# SOC_SDRAM.net
KiCad netlist of a schematic drawn in Altium Designer
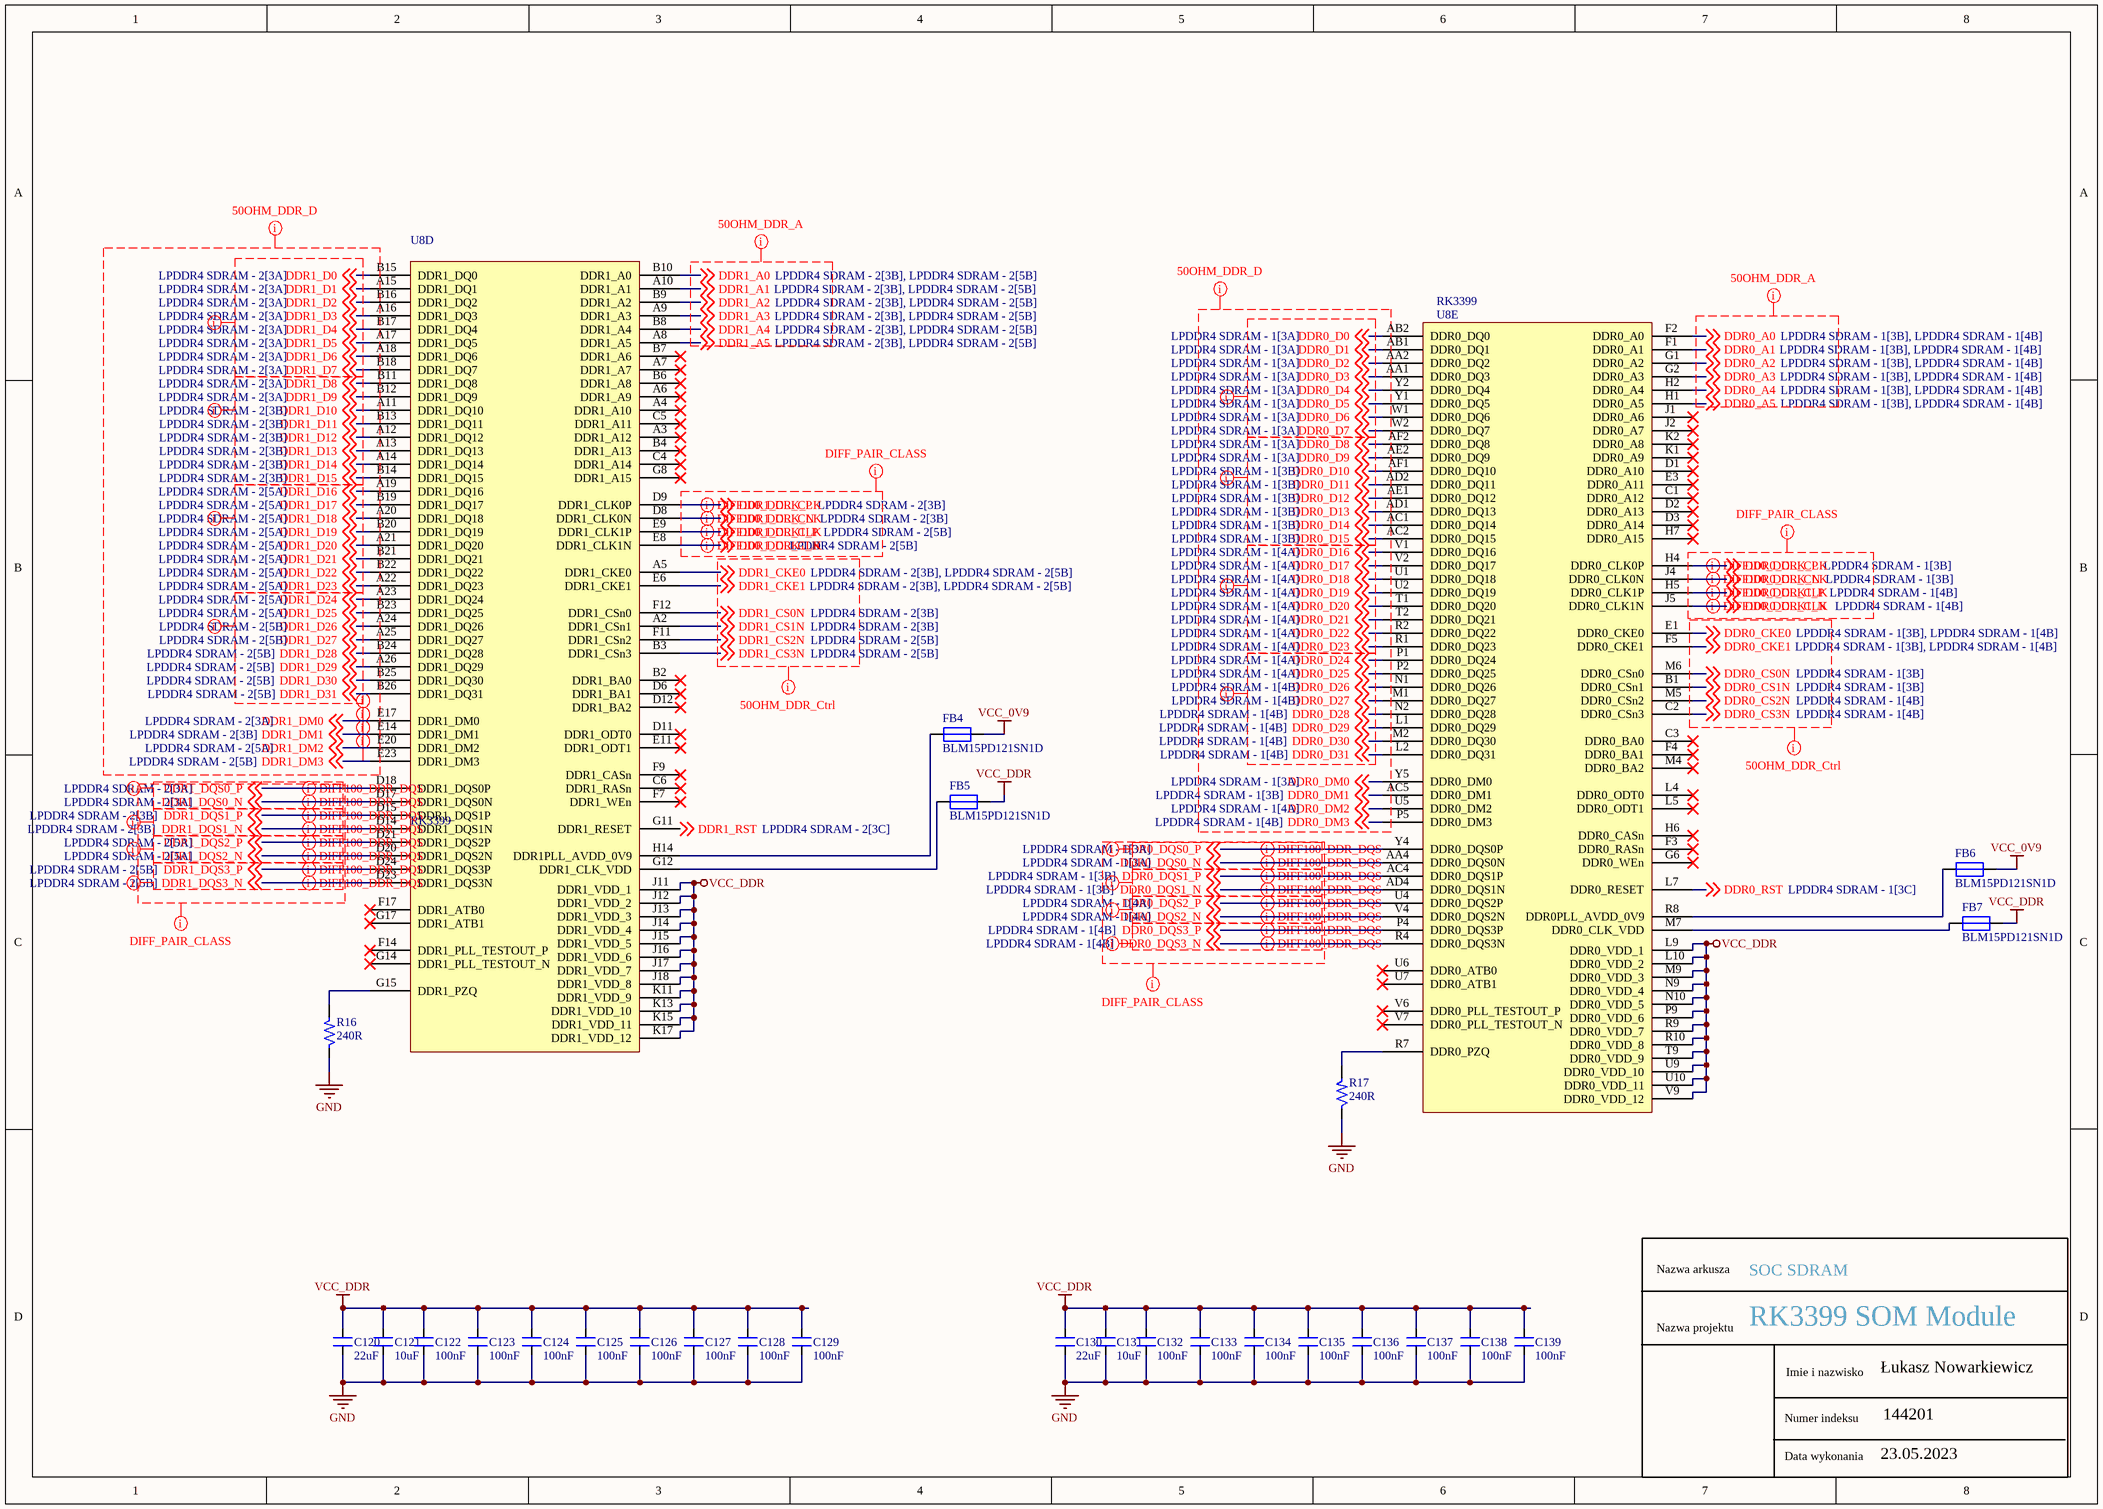
[diagram p0: SOC SDRAM.SchDoc]

(export (version "E")
  (design (tool "Eeschema 10.0.6"))
  (components
    (comp (ref "C120")
      (value "22uF")
      (footprint "CAP_0603")
      (description "22µF ±20% 10V Ceramic Capacitor X5R 0603 (1608 Metric)")
      (fields
        (field (name "MANUFACTURER") "Murata Electronics")
        (field (name "MANUFACTURER PART NUMBER") "GRM188R61A226ME15D")
      )
      (libsource (lib "EsteemPCB_SOM_Course_intlib") (part "CAP_22uF-10V-20%-0603"))
    )
    (comp (ref "C121")
      (value "10uF")
      (footprint "CAP_0603")
      (description "10µF ±10% 10V Ceramic Capacitor X5R 0603 (1608 Metric)")
      (fields
        (field (name "MANUFACTURER PART NUMBER") "GRM188R61A106KE69J")
        (field (name "MANUFACTURER") "Murata Electronics")
      )
      (libsource (lib "EsteemPCB_SOM_Course_intlib") (part "CAP_10uF-10V-10%-0603"))
    )
    (comp (ref "C122")
      (value "100nF")
      (footprint "CAP_0402")
      (description "0.1µF ±10% 10V Ceramic Capacitor X7R 0402 (1005 Metric)")
      (fields
        (field (name "MANUFACTURER") "Yageo")
        (field (name "MANUFACTURER PART NUMBER") "CC0402KRX7R6BB104")
      )
      (libsource (lib "EsteemPCB_SOM_Course_intlib") (part "CAP_100nF-10V-10%-0402"))
    )
    (comp (ref "C123")
      (value "100nF")
      (footprint "CAP_0402")
      (description "0.1µF ±10% 10V Ceramic Capacitor X7R 0402 (1005 Metric)")
      (fields
        (field (name "MANUFACTURER") "Yageo")
        (field (name "MANUFACTURER PART NUMBER") "CC0402KRX7R6BB104")
      )
      (libsource (lib "EsteemPCB_SOM_Course_intlib") (part "CAP_100nF-10V-10%-0402"))
    )
    (comp (ref "C124")
      (value "100nF")
      (footprint "CAP_0402")
      (description "0.1µF ±10% 10V Ceramic Capacitor X7R 0402 (1005 Metric)")
      (fields
        (field (name "MANUFACTURER") "Yageo")
        (field (name "MANUFACTURER PART NUMBER") "CC0402KRX7R6BB104")
      )
      (libsource (lib "EsteemPCB_SOM_Course_intlib") (part "CAP_100nF-10V-10%-0402"))
    )
    (comp (ref "C125")
      (value "100nF")
      (footprint "CAP_0402")
      (description "0.1µF ±10% 10V Ceramic Capacitor X7R 0402 (1005 Metric)")
      (fields
        (field (name "MANUFACTURER") "Yageo")
        (field (name "MANUFACTURER PART NUMBER") "CC0402KRX7R6BB104")
      )
      (libsource (lib "EsteemPCB_SOM_Course_intlib") (part "CAP_100nF-10V-10%-0402"))
    )
    (comp (ref "C126")
      (value "100nF")
      (footprint "CAP_0402")
      (description "0.1µF ±10% 10V Ceramic Capacitor X7R 0402 (1005 Metric)")
      (fields
        (field (name "MANUFACTURER") "Yageo")
        (field (name "MANUFACTURER PART NUMBER") "CC0402KRX7R6BB104")
      )
      (libsource (lib "EsteemPCB_SOM_Course_intlib") (part "CAP_100nF-10V-10%-0402"))
    )
    (comp (ref "C127")
      (value "100nF")
      (footprint "CAP_0402")
      (description "0.1µF ±10% 10V Ceramic Capacitor X7R 0402 (1005 Metric)")
      (fields
        (field (name "MANUFACTURER") "Yageo")
        (field (name "MANUFACTURER PART NUMBER") "CC0402KRX7R6BB104")
      )
      (libsource (lib "EsteemPCB_SOM_Course_intlib") (part "CAP_100nF-10V-10%-0402"))
    )
    (comp (ref "C128")
      (value "100nF")
      (footprint "CAP_0402")
      (description "0.1µF ±10% 10V Ceramic Capacitor X7R 0402 (1005 Metric)")
      (fields
        (field (name "MANUFACTURER") "Yageo")
        (field (name "MANUFACTURER PART NUMBER") "CC0402KRX7R6BB104")
      )
      (libsource (lib "EsteemPCB_SOM_Course_intlib") (part "CAP_100nF-10V-10%-0402"))
    )
    (comp (ref "C129")
      (value "100nF")
      (footprint "CAP_0402")
      (description "0.1µF ±10% 10V Ceramic Capacitor X7R 0402 (1005 Metric)")
      (fields
        (field (name "MANUFACTURER") "Yageo")
        (field (name "MANUFACTURER PART NUMBER") "CC0402KRX7R6BB104")
      )
      (libsource (lib "EsteemPCB_SOM_Course_intlib") (part "CAP_100nF-10V-10%-0402"))
    )
    (comp (ref "C130")
      (value "22uF")
      (footprint "CAP_0603")
      (description "22µF ±20% 10V Ceramic Capacitor X5R 0603 (1608 Metric)")
      (fields
        (field (name "MANUFACTURER") "Murata Electronics")
        (field (name "MANUFACTURER PART NUMBER") "GRM188R61A226ME15D")
      )
      (libsource (lib "EsteemPCB_SOM_Course_intlib") (part "CAP_22uF-10V-20%-0603"))
    )
    (comp (ref "C131")
      (value "10uF")
      (footprint "CAP_0603")
      (description "10µF ±10% 10V Ceramic Capacitor X5R 0603 (1608 Metric)")
      (fields
        (field (name "MANUFACTURER PART NUMBER") "GRM188R61A106KE69J")
        (field (name "MANUFACTURER") "Murata Electronics")
      )
      (libsource (lib "EsteemPCB_SOM_Course_intlib") (part "CAP_10uF-10V-10%-0603"))
    )
    (comp (ref "C132")
      (value "100nF")
      (footprint "CAP_0402")
      (description "0.1µF ±10% 10V Ceramic Capacitor X7R 0402 (1005 Metric)")
      (fields
        (field (name "MANUFACTURER") "Yageo")
        (field (name "MANUFACTURER PART NUMBER") "CC0402KRX7R6BB104")
      )
      (libsource (lib "EsteemPCB_SOM_Course_intlib") (part "CAP_100nF-10V-10%-0402"))
    )
    (comp (ref "C133")
      (value "100nF")
      (footprint "CAP_0402")
      (description "0.1µF ±10% 10V Ceramic Capacitor X7R 0402 (1005 Metric)")
      (fields
        (field (name "MANUFACTURER") "Yageo")
        (field (name "MANUFACTURER PART NUMBER") "CC0402KRX7R6BB104")
      )
      (libsource (lib "EsteemPCB_SOM_Course_intlib") (part "CAP_100nF-10V-10%-0402"))
    )
    (comp (ref "C134")
      (value "100nF")
      (footprint "CAP_0402")
      (description "0.1µF ±10% 10V Ceramic Capacitor X7R 0402 (1005 Metric)")
      (fields
        (field (name "MANUFACTURER") "Yageo")
        (field (name "MANUFACTURER PART NUMBER") "CC0402KRX7R6BB104")
      )
      (libsource (lib "EsteemPCB_SOM_Course_intlib") (part "CAP_100nF-10V-10%-0402"))
    )
    (comp (ref "C135")
      (value "100nF")
      (footprint "CAP_0402")
      (description "0.1µF ±10% 10V Ceramic Capacitor X7R 0402 (1005 Metric)")
      (fields
        (field (name "MANUFACTURER") "Yageo")
        (field (name "MANUFACTURER PART NUMBER") "CC0402KRX7R6BB104")
      )
      (libsource (lib "EsteemPCB_SOM_Course_intlib") (part "CAP_100nF-10V-10%-0402"))
    )
    (comp (ref "C136")
      (value "100nF")
      (footprint "CAP_0402")
      (description "0.1µF ±10% 10V Ceramic Capacitor X7R 0402 (1005 Metric)")
      (fields
        (field (name "MANUFACTURER") "Yageo")
        (field (name "MANUFACTURER PART NUMBER") "CC0402KRX7R6BB104")
      )
      (libsource (lib "EsteemPCB_SOM_Course_intlib") (part "CAP_100nF-10V-10%-0402"))
    )
    (comp (ref "C137")
      (value "100nF")
      (footprint "CAP_0402")
      (description "0.1µF ±10% 10V Ceramic Capacitor X7R 0402 (1005 Metric)")
      (fields
        (field (name "MANUFACTURER") "Yageo")
        (field (name "MANUFACTURER PART NUMBER") "CC0402KRX7R6BB104")
      )
      (libsource (lib "EsteemPCB_SOM_Course_intlib") (part "CAP_100nF-10V-10%-0402"))
    )
    (comp (ref "C138")
      (value "100nF")
      (footprint "CAP_0402")
      (description "0.1µF ±10% 10V Ceramic Capacitor X7R 0402 (1005 Metric)")
      (fields
        (field (name "MANUFACTURER") "Yageo")
        (field (name "MANUFACTURER PART NUMBER") "CC0402KRX7R6BB104")
      )
      (libsource (lib "EsteemPCB_SOM_Course_intlib") (part "CAP_100nF-10V-10%-0402"))
    )
    (comp (ref "C139")
      (value "100nF")
      (footprint "CAP_0402")
      (description "0.1µF ±10% 10V Ceramic Capacitor X7R 0402 (1005 Metric)")
      (fields
        (field (name "MANUFACTURER") "Yageo")
        (field (name "MANUFACTURER PART NUMBER") "CC0402KRX7R6BB104")
      )
      (libsource (lib "EsteemPCB_SOM_Course_intlib") (part "CAP_100nF-10V-10%-0402"))
    )
    (comp (ref "FB4")
      (value "BLM15PD121SN1D")
      (footprint "RES_0402")
      (description "120 Ohms @ 100MHz 1 Power Line Ferrite Bead 0402 (1005 Metric) 1.3A 90mOhm")
      (fields (field (name "MANUFACTURER") "Murata Electronics"))
      (libsource (lib "RK3399 _Module_Schlib") (part "FB_120R-1.3A-100Mhz-0402"))
    )
    (comp (ref "FB5")
      (value "BLM15PD121SN1D")
      (footprint "RES_0402")
      (description "120 Ohms @ 100MHz 1 Power Line Ferrite Bead 0402 (1005 Metric) 1.3A 90mOhm")
      (fields (field (name "MANUFACTURER") "Murata Electronics"))
      (libsource (lib "RK3399 _Module_Schlib") (part "FB_120R-1.3A-100Mhz-0402"))
    )
    (comp (ref "FB6")
      (value "BLM15PD121SN1D")
      (footprint "RES_0402")
      (description "120 Ohms @ 100MHz 1 Power Line Ferrite Bead 0402 (1005 Metric) 1.3A 90mOhm")
      (fields (field (name "MANUFACTURER") "Murata Electronics"))
      (libsource (lib "RK3399 _Module_Schlib") (part "FB_120R-1.3A-100Mhz-0402"))
    )
    (comp (ref "FB7")
      (value "BLM15PD121SN1D")
      (footprint "RES_0402")
      (description "120 Ohms @ 100MHz 1 Power Line Ferrite Bead 0402 (1005 Metric) 1.3A 90mOhm")
      (fields (field (name "MANUFACTURER") "Murata Electronics"))
      (libsource (lib "RK3399 _Module_Schlib") (part "FB_120R-1.3A-100Mhz-0402"))
    )
    (comp (ref "R16")
      (value "240R")
      (footprint "RES_0201")
      (description "240 Ohms ±1% 0.05W, 1/20W Chip Resistor 0201 (0603 Metric) Thick Film")
      (fields
        (field (name "MANUFACTURER") "Yageo")
        (field (name "MANUFACTURER PART NUMBER") "RC0201FR-07240RL")
      )
      (libsource (lib "EsteemPCB_SOM_Course_intlib") (part "RES_240R-0.05W-1%-0201"))
    )
    (comp (ref "R17")
      (value "240R")
      (footprint "RES_0201")
      (description "240 Ohms ±1% 0.05W, 1/20W Chip Resistor 0201 (0603 Metric) Thick Film")
      (fields
        (field (name "MANUFACTURER") "Yageo")
        (field (name "MANUFACTURER PART NUMBER") "RC0201FR-07240RL")
      )
      (libsource (lib "EsteemPCB_SOM_Course_intlib") (part "RES_240R-0.05W-1%-0201"))
    )
    (comp (ref "U8")
      (value "RK3399")
      (footprint "FBGA828_23_826X826")
      (description "RK3399 is a low power, high performance processor for computing, personal mobile.")
      (fields (field (name "MANUFACTURER") "Rockchip"))
      (libsource (lib "EsteemPCB_SOM_Course_intlib") (part "IC_RK3399-FCBGA828"))
    )
  )
  (nets
    (net (code "1") (name "DDR0_A0") (class "Default")
      (node (ref "U8") (pin "F2") (pinfunction "DDR0_A0_F2") (pintype "passive"))
    )
    (net (code "2") (name "DDR0_A1") (class "Default")
      (node (ref "U8") (pin "F1") (pinfunction "DDR0_A1_F1") (pintype "passive"))
    )
    (net (code "3") (name "DDR0_A2") (class "Default")
      (node (ref "U8") (pin "G1") (pinfunction "DDR0_A2_G1") (pintype "passive"))
    )
    (net (code "4") (name "DDR0_A3") (class "Default")
      (node (ref "U8") (pin "G2") (pinfunction "DDR0_A3_G2") (pintype "passive"))
    )
    (net (code "5") (name "DDR0_A4") (class "Default")
      (node (ref "U8") (pin "H2") (pinfunction "DDR0_A4_H2") (pintype "passive"))
    )
    (net (code "6") (name "DDR0_A5") (class "Default")
      (node (ref "U8") (pin "H1") (pinfunction "DDR0_A5_H1") (pintype "passive"))
    )
    (net (code "7") (name "DDR0_CKE0") (class "Default")
      (node (ref "U8") (pin "E1") (pinfunction "DDR0_CKE0_E1") (pintype "passive"))
    )
    (net (code "8") (name "DDR0_CKE1") (class "Default")
      (node (ref "U8") (pin "F5") (pinfunction "DDR0_CKE1_F5") (pintype "passive"))
    )
    (net (code "9") (name "DDR0_CLK1_N") (class "Default")
      (node (ref "U8") (pin "J5") (pinfunction "DDR0_CLK1N_J5") (pintype "passive"))
    )
    (net (code "10") (name "DDR0_CLK1_P") (class "Default")
      (node (ref "U8") (pin "H5") (pinfunction "DDR0_CLK1P_H5") (pintype "passive"))
    )
    (net (code "11") (name "DDR0_CLK_N") (class "Default")
      (node (ref "U8") (pin "J4") (pinfunction "DDR0_CLK0N_J4") (pintype "passive"))
    )
    (net (code "12") (name "DDR0_CLK_P") (class "Default")
      (node (ref "U8") (pin "H4") (pinfunction "DDR0_CLK0P_H4") (pintype "passive"))
    )
    (net (code "13") (name "DDR0_CS0N") (class "Default")
      (node (ref "U8") (pin "M6") (pinfunction "DDR0_CSn0_M6") (pintype "passive"))
    )
    (net (code "14") (name "DDR0_CS1N") (class "Default")
      (node (ref "U8") (pin "B1") (pinfunction "DDR0_CSn1_B1") (pintype "passive"))
    )
    (net (code "15") (name "DDR0_CS2N") (class "Default")
      (node (ref "U8") (pin "M5") (pinfunction "DDR0_CSn2_M5") (pintype "passive"))
    )
    (net (code "16") (name "DDR0_CS3N") (class "Default")
      (node (ref "U8") (pin "C2") (pinfunction "DDR0_CSn3_C2") (pintype "passive"))
    )
    (net (code "17") (name "DDR0_D0") (class "Default")
      (node (ref "U8") (pin "AB2") (pinfunction "DDR0_DQ0_AB2") (pintype "passive"))
    )
    (net (code "18") (name "DDR0_D1") (class "Default")
      (node (ref "U8") (pin "AB1") (pinfunction "DDR0_DQ1_AB1") (pintype "passive"))
    )
    (net (code "19") (name "DDR0_D2") (class "Default")
      (node (ref "U8") (pin "AA2") (pinfunction "DDR0_DQ2_AA2") (pintype "passive"))
    )
    (net (code "20") (name "DDR0_D3") (class "Default")
      (node (ref "U8") (pin "AA1") (pinfunction "DDR0_DQ3_AA1") (pintype "passive"))
    )
    (net (code "21") (name "DDR0_D4") (class "Default")
      (node (ref "U8") (pin "Y2") (pinfunction "DDR0_DQ4_Y2") (pintype "passive"))
    )
    (net (code "22") (name "DDR0_D5") (class "Default")
      (node (ref "U8") (pin "Y1") (pinfunction "DDR0_DQ5_Y1") (pintype "passive"))
    )
    (net (code "23") (name "DDR0_D6") (class "Default")
      (node (ref "U8") (pin "W1") (pinfunction "DDR0_DQ6_W1") (pintype "passive"))
    )
    (net (code "24") (name "DDR0_D7") (class "Default")
      (node (ref "U8") (pin "W2") (pinfunction "DDR0_DQ7_W2") (pintype "passive"))
    )
    (net (code "25") (name "DDR0_D8") (class "Default")
      (node (ref "U8") (pin "AF2") (pinfunction "DDR0_DQ8_AF2") (pintype "passive"))
    )
    (net (code "26") (name "DDR0_D9") (class "Default")
      (node (ref "U8") (pin "AE2") (pinfunction "DDR0_DQ9_AE2") (pintype "passive"))
    )
    (net (code "27") (name "DDR0_D10") (class "Default")
      (node (ref "U8") (pin "AF1") (pinfunction "DDR0_DQ10_AF1") (pintype "passive"))
    )
    (net (code "28") (name "DDR0_D11") (class "Default")
      (node (ref "U8") (pin "AD2") (pinfunction "DDR0_DQ11_AD2") (pintype "passive"))
    )
    (net (code "29") (name "DDR0_D12") (class "Default")
      (node (ref "U8") (pin "AE1") (pinfunction "DDR0_DQ12_AE1") (pintype "passive"))
    )
    (net (code "30") (name "DDR0_D13") (class "Default")
      (node (ref "U8") (pin "AD1") (pinfunction "DDR0_DQ13_AD1") (pintype "passive"))
    )
    (net (code "31") (name "DDR0_D14") (class "Default")
      (node (ref "U8") (pin "AC1") (pinfunction "DDR0_DQ14_AC1") (pintype "passive"))
    )
    (net (code "32") (name "DDR0_D15") (class "Default")
      (node (ref "U8") (pin "AC2") (pinfunction "DDR0_DQ15_AC2") (pintype "passive"))
    )
    (net (code "33") (name "DDR0_D16") (class "Default")
      (node (ref "U8") (pin "V1") (pinfunction "DDR0_DQ16_V1") (pintype "passive"))
    )
    (net (code "34") (name "DDR0_D17") (class "Default")
      (node (ref "U8") (pin "V2") (pinfunction "DDR0_DQ17_V2") (pintype "passive"))
    )
    (net (code "35") (name "DDR0_D18") (class "Default")
      (node (ref "U8") (pin "U1") (pinfunction "DDR0_DQ18_U1") (pintype "passive"))
    )
    (net (code "36") (name "DDR0_D19") (class "Default")
      (node (ref "U8") (pin "U2") (pinfunction "DDR0_DQ19_U2") (pintype "passive"))
    )
    (net (code "37") (name "DDR0_D20") (class "Default")
      (node (ref "U8") (pin "T1") (pinfunction "DDR0_DQ20_T1") (pintype "passive"))
    )
    (net (code "38") (name "DDR0_D21") (class "Default")
      (node (ref "U8") (pin "T2") (pinfunction "DDR0_DQ21_T2") (pintype "passive"))
    )
    (net (code "39") (name "DDR0_D22") (class "Default")
      (node (ref "U8") (pin "R2") (pinfunction "DDR0_DQ22_R2") (pintype "passive"))
    )
    (net (code "40") (name "DDR0_D23") (class "Default")
      (node (ref "U8") (pin "R1") (pinfunction "DDR0_DQ23_R1") (pintype "passive"))
    )
    (net (code "41") (name "DDR0_D24") (class "Default")
      (node (ref "U8") (pin "P1") (pinfunction "DDR0_DQ24_P1") (pintype "passive"))
    )
    (net (code "42") (name "DDR0_D25") (class "Default")
      (node (ref "U8") (pin "P2") (pinfunction "DDR0_DQ25_P2") (pintype "passive"))
    )
    (net (code "43") (name "DDR0_D26") (class "Default")
      (node (ref "U8") (pin "N1") (pinfunction "DDR0_DQ26_N1") (pintype "passive"))
    )
    (net (code "44") (name "DDR0_D27") (class "Default")
      (node (ref "U8") (pin "M1") (pinfunction "DDR0_DQ27_M1") (pintype "passive"))
    )
    (net (code "45") (name "DDR0_D28") (class "Default")
      (node (ref "U8") (pin "N2") (pinfunction "DDR0_DQ28_N2") (pintype "passive"))
    )
    (net (code "46") (name "DDR0_D29") (class "Default")
      (node (ref "U8") (pin "L1") (pinfunction "DDR0_DQ29_L1") (pintype "passive"))
    )
    (net (code "47") (name "DDR0_D30") (class "Default")
      (node (ref "U8") (pin "M2") (pinfunction "DDR0_DQ30_M2") (pintype "passive"))
    )
    (net (code "48") (name "DDR0_D31") (class "Default")
      (node (ref "U8") (pin "L2") (pinfunction "DDR0_DQ31_L2") (pintype "passive"))
    )
    (net (code "49") (name "DDR0_DM0") (class "Default")
      (node (ref "U8") (pin "Y5") (pinfunction "DDR0_DM0_Y5") (pintype "passive"))
    )
    (net (code "50") (name "DDR0_DM1") (class "Default")
      (node (ref "U8") (pin "AC5") (pinfunction "DDR0_DM1_AC5") (pintype "passive"))
    )
    (net (code "51") (name "DDR0_DM2") (class "Default")
      (node (ref "U8") (pin "U5") (pinfunction "DDR0_DM2_U5") (pintype "passive"))
    )
    (net (code "52") (name "DDR0_DM3") (class "Default")
      (node (ref "U8") (pin "P5") (pinfunction "DDR0_DM3_P5") (pintype "passive"))
    )
    (net (code "53") (name "DDR0_DQS0_N") (class "Default")
      (node (ref "U8") (pin "AA4") (pinfunction "DDR0_DQS0N_AA4") (pintype "passive"))
    )
    (net (code "54") (name "DDR0_DQS0_P") (class "Default")
      (node (ref "U8") (pin "Y4") (pinfunction "DDR0_DQS0P_Y4") (pintype "passive"))
    )
    (net (code "55") (name "DDR0_DQS1_N") (class "Default")
      (node (ref "U8") (pin "AD4") (pinfunction "DDR0_DQS1N_AD4") (pintype "passive"))
    )
    (net (code "56") (name "DDR0_DQS1_P") (class "Default")
      (node (ref "U8") (pin "AC4") (pinfunction "DDR0_DQS1P_AC4") (pintype "passive"))
    )
    (net (code "57") (name "DDR0_DQS2_N") (class "Default")
      (node (ref "U8") (pin "V4") (pinfunction "DDR0_DQS2N_V4") (pintype "passive"))
    )
    (net (code "58") (name "DDR0_DQS2_P") (class "Default")
      (node (ref "U8") (pin "U4") (pinfunction "DDR0_DQS2P_U4") (pintype "passive"))
    )
    (net (code "59") (name "DDR0_DQS3_N") (class "Default")
      (node (ref "U8") (pin "R4") (pinfunction "DDR0_DQS3N_R4") (pintype "passive"))
    )
    (net (code "60") (name "DDR0_DQS3_P") (class "Default")
      (node (ref "U8") (pin "P4") (pinfunction "DDR0_DQS3P_P4") (pintype "passive"))
    )
    (net (code "61") (name "DDR0_RST") (class "Default")
      (node (ref "U8") (pin "L7") (pinfunction "DDR0_RESET_L7") (pintype "passive"))
    )
    (net (code "62") (name "DDR1_A0") (class "Default")
      (node (ref "U8") (pin "B10") (pinfunction "DDR1_A0_B10") (pintype "passive"))
    )
    (net (code "63") (name "DDR1_A1") (class "Default")
      (node (ref "U8") (pin "A10") (pinfunction "DDR1_A1_A10") (pintype "passive"))
    )
    (net (code "64") (name "DDR1_A2") (class "Default")
      (node (ref "U8") (pin "B9") (pinfunction "DDR1_A2_B9") (pintype "passive"))
    )
    (net (code "65") (name "DDR1_A3") (class "Default")
      (node (ref "U8") (pin "A9") (pinfunction "DDR1_A3_A9") (pintype "passive"))
    )
    (net (code "66") (name "DDR1_A4") (class "Default")
      (node (ref "U8") (pin "B8") (pinfunction "DDR1_A4_B8") (pintype "passive"))
    )
    (net (code "67") (name "DDR1_A5") (class "Default")
      (node (ref "U8") (pin "A8") (pinfunction "DDR1_A5_A8") (pintype "passive"))
    )
    (net (code "68") (name "DDR1_CKE0") (class "Default")
      (node (ref "U8") (pin "A5") (pinfunction "DDR1_CKE0_A5") (pintype "passive"))
    )
    (net (code "69") (name "DDR1_CKE1") (class "Default")
      (node (ref "U8") (pin "E6") (pinfunction "DDR1_CKE1_E6") (pintype "passive"))
    )
    (net (code "70") (name "DDR1_CLK1_N") (class "Default")
      (node (ref "U8") (pin "E8") (pinfunction "DDR1_CLK1N_E8") (pintype "passive"))
    )
    (net (code "71") (name "DDR1_CLK1_P") (class "Default")
      (node (ref "U8") (pin "E9") (pinfunction "DDR1_CLK1P_E9") (pintype "passive"))
    )
    (net (code "72") (name "DDR1_CLK_N") (class "Default")
      (node (ref "U8") (pin "D8") (pinfunction "DDR1_CLK0N_D8") (pintype "passive"))
    )
    (net (code "73") (name "DDR1_CLK_P") (class "Default")
      (node (ref "U8") (pin "D9") (pinfunction "DDR1_CLK0P_D9") (pintype "passive"))
    )
    (net (code "74") (name "DDR1_CS0N") (class "Default")
      (node (ref "U8") (pin "F12") (pinfunction "DDR1_CSn0_F12") (pintype "passive"))
    )
    (net (code "75") (name "DDR1_CS1N") (class "Default")
      (node (ref "U8") (pin "A2") (pinfunction "DDR1_CSn1_A2") (pintype "passive"))
    )
    (net (code "76") (name "DDR1_CS2N") (class "Default")
      (node (ref "U8") (pin "F11") (pinfunction "DDR1_CSn2_F11") (pintype "passive"))
    )
    (net (code "77") (name "DDR1_CS3N") (class "Default")
      (node (ref "U8") (pin "B3") (pinfunction "DDR1_CSn3_B3") (pintype "passive"))
    )
    (net (code "78") (name "DDR1_D0") (class "Default")
      (node (ref "U8") (pin "B15") (pinfunction "DDR1_DQ0_B15") (pintype "passive"))
    )
    (net (code "79") (name "DDR1_D1") (class "Default")
      (node (ref "U8") (pin "A15") (pinfunction "DDR1_DQ1_A15") (pintype "passive"))
    )
    (net (code "80") (name "DDR1_D2") (class "Default")
      (node (ref "U8") (pin "B16") (pinfunction "DDR1_DQ2_B16") (pintype "passive"))
    )
    (net (code "81") (name "DDR1_D3") (class "Default")
      (node (ref "U8") (pin "A16") (pinfunction "DDR1_DQ3_A16") (pintype "passive"))
    )
    (net (code "82") (name "DDR1_D4") (class "Default")
      (node (ref "U8") (pin "B17") (pinfunction "DDR1_DQ4_B17") (pintype "passive"))
    )
    (net (code "83") (name "DDR1_D5") (class "Default")
      (node (ref "U8") (pin "A17") (pinfunction "DDR1_DQ5_A17") (pintype "passive"))
    )
    (net (code "84") (name "DDR1_D6") (class "Default")
      (node (ref "U8") (pin "A18") (pinfunction "DDR1_DQ6_A18") (pintype "passive"))
    )
    (net (code "85") (name "DDR1_D7") (class "Default")
      (node (ref "U8") (pin "B18") (pinfunction "DDR1_DQ7_B18") (pintype "passive"))
    )
    (net (code "86") (name "DDR1_D8") (class "Default")
      (node (ref "U8") (pin "B11") (pinfunction "DDR1_DQ8_B11") (pintype "passive"))
    )
    (net (code "87") (name "DDR1_D9") (class "Default")
      (node (ref "U8") (pin "B12") (pinfunction "DDR1_DQ9_B12") (pintype "passive"))
    )
    (net (code "88") (name "DDR1_D10") (class "Default")
      (node (ref "U8") (pin "A11") (pinfunction "DDR1_DQ10_A11") (pintype "passive"))
    )
    (net (code "89") (name "DDR1_D11") (class "Default")
      (node (ref "U8") (pin "B13") (pinfunction "DDR1_DQ11_B13") (pintype "passive"))
    )
    (net (code "90") (name "DDR1_D12") (class "Default")
      (node (ref "U8") (pin "A12") (pinfunction "DDR1_DQ12_A12") (pintype "passive"))
    )
    (net (code "91") (name "DDR1_D13") (class "Default")
      (node (ref "U8") (pin "A13") (pinfunction "DDR1_DQ13_A13") (pintype "passive"))
    )
    (net (code "92") (name "DDR1_D14") (class "Default")
      (node (ref "U8") (pin "A14") (pinfunction "DDR1_DQ14_A14") (pintype "passive"))
    )
    (net (code "93") (name "DDR1_D15") (class "Default")
      (node (ref "U8") (pin "B14") (pinfunction "DDR1_DQ15_B14") (pintype "passive"))
    )
    (net (code "94") (name "DDR1_D16") (class "Default")
      (node (ref "U8") (pin "A19") (pinfunction "DDR1_DQ16_A19") (pintype "passive"))
    )
    (net (code "95") (name "DDR1_D17") (class "Default")
      (node (ref "U8") (pin "B19") (pinfunction "DDR1_DQ17_B19") (pintype "passive"))
    )
    (net (code "96") (name "DDR1_D18") (class "Default")
      (node (ref "U8") (pin "A20") (pinfunction "DDR1_DQ18_A20") (pintype "passive"))
    )
    (net (code "97") (name "DDR1_D19") (class "Default")
      (node (ref "U8") (pin "B20") (pinfunction "DDR1_DQ19_B20") (pintype "passive"))
    )
    (net (code "98") (name "DDR1_D20") (class "Default")
      (node (ref "U8") (pin "A21") (pinfunction "DDR1_DQ20_A21") (pintype "passive"))
    )
    (net (code "99") (name "DDR1_D21") (class "Default")
      (node (ref "U8") (pin "B21") (pinfunction "DDR1_DQ21_B21") (pintype "passive"))
    )
    (net (code "100") (name "DDR1_D22") (class "Default")
      (node (ref "U8") (pin "B22") (pinfunction "DDR1_DQ22_B22") (pintype "passive"))
    )
    (net (code "101") (name "DDR1_D23") (class "Default")
      (node (ref "U8") (pin "A22") (pinfunction "DDR1_DQ23_A22") (pintype "passive"))
    )
    (net (code "102") (name "DDR1_D24") (class "Default")
      (node (ref "U8") (pin "A23") (pinfunction "DDR1_DQ24_A23") (pintype "passive"))
    )
    (net (code "103") (name "DDR1_D25") (class "Default")
      (node (ref "U8") (pin "B23") (pinfunction "DDR1_DQ25_B23") (pintype "passive"))
    )
    (net (code "104") (name "DDR1_D26") (class "Default")
      (node (ref "U8") (pin "A24") (pinfunction "DDR1_DQ26_A24") (pintype "passive"))
    )
    (net (code "105") (name "DDR1_D27") (class "Default")
      (node (ref "U8") (pin "A25") (pinfunction "DDR1_DQ27_A25") (pintype "passive"))
    )
    (net (code "106") (name "DDR1_D28") (class "Default")
      (node (ref "U8") (pin "B24") (pinfunction "DDR1_DQ28_B24") (pintype "passive"))
    )
    (net (code "107") (name "DDR1_D29") (class "Default")
      (node (ref "U8") (pin "A26") (pinfunction "DDR1_DQ29_A26") (pintype "passive"))
    )
    (net (code "108") (name "DDR1_D30") (class "Default")
      (node (ref "U8") (pin "B25") (pinfunction "DDR1_DQ30_B25") (pintype "passive"))
    )
    (net (code "109") (name "DDR1_D31") (class "Default")
      (node (ref "U8") (pin "B26") (pinfunction "DDR1_DQ31_B26") (pintype "passive"))
    )
    (net (code "110") (name "DDR1_DM0") (class "Default")
      (node (ref "U8") (pin "E17") (pinfunction "DDR1_DM0_E17") (pintype "passive"))
    )
    (net (code "111") (name "DDR1_DM1") (class "Default")
      (node (ref "U8") (pin "E14") (pinfunction "DDR1_DM1_E14") (pintype "passive"))
    )
    (net (code "112") (name "DDR1_DM2") (class "Default")
      (node (ref "U8") (pin "E20") (pinfunction "DDR1_DM2_E20") (pintype "passive"))
    )
    (net (code "113") (name "DDR1_DM3") (class "Default")
      (node (ref "U8") (pin "E23") (pinfunction "DDR1_DM3_E23") (pintype "passive"))
    )
    (net (code "114") (name "DDR1_DQS0_N") (class "Default")
      (node (ref "U8") (pin "D17") (pinfunction "DDR1_DQS0N_D17") (pintype "passive"))
    )
    (net (code "115") (name "DDR1_DQS0_P") (class "Default")
      (node (ref "U8") (pin "D18") (pinfunction "DDR1_DQS0P_D18") (pintype "passive"))
    )
    (net (code "116") (name "DDR1_DQS1_N") (class "Default")
      (node (ref "U8") (pin "D14") (pinfunction "DDR1_DQS1N_D14") (pintype "passive"))
    )
    (net (code "117") (name "DDR1_DQS1_P") (class "Default")
      (node (ref "U8") (pin "D15") (pinfunction "DDR1_DQS1P_D15") (pintype "passive"))
    )
    (net (code "118") (name "DDR1_DQS2_N") (class "Default")
      (node (ref "U8") (pin "D20") (pinfunction "DDR1_DQS2N_D20") (pintype "passive"))
    )
    (net (code "119") (name "DDR1_DQS2_P") (class "Default")
      (node (ref "U8") (pin "D21") (pinfunction "DDR1_DQS2P_D21") (pintype "passive"))
    )
    (net (code "120") (name "DDR1_DQS3_N") (class "Default")
      (node (ref "U8") (pin "D23") (pinfunction "DDR1_DQS3N_D23") (pintype "passive"))
    )
    (net (code "121") (name "DDR1_DQS3_P") (class "Default")
      (node (ref "U8") (pin "D24") (pinfunction "DDR1_DQS3P_D24") (pintype "passive"))
    )
    (net (code "122") (name "DDR1_RST") (class "Default")
      (node (ref "U8") (pin "G11") (pinfunction "DDR1_RESET_G11") (pintype "passive"))
    )
    (net (code "123") (name "GND") (class "Default")
      (node (ref "C120") (pin "1") (pinfunction "1_1") (pintype "passive"))
      (node (ref "C121") (pin "1") (pinfunction "1_1") (pintype "passive"))
      (node (ref "C122") (pin "1") (pinfunction "1_1") (pintype "passive"))
      (node (ref "C123") (pin "1") (pinfunction "1_1") (pintype "passive"))
      (node (ref "C124") (pin "1") (pinfunction "1_1") (pintype "passive"))
      (node (ref "C125") (pin "1") (pinfunction "1_1") (pintype "passive"))
      (node (ref "C126") (pin "1") (pinfunction "1_1") (pintype "passive"))
      (node (ref "C127") (pin "1") (pinfunction "1_1") (pintype "passive"))
      (node (ref "C128") (pin "1") (pinfunction "1_1") (pintype "passive"))
      (node (ref "C129") (pin "1") (pinfunction "1_1") (pintype "passive"))
      (node (ref "C130") (pin "1") (pinfunction "1_1") (pintype "passive"))
      (node (ref "C131") (pin "1") (pinfunction "1_1") (pintype "passive"))
      (node (ref "C132") (pin "1") (pinfunction "1_1") (pintype "passive"))
      (node (ref "C133") (pin "1") (pinfunction "1_1") (pintype "passive"))
      (node (ref "C134") (pin "1") (pinfunction "1_1") (pintype "passive"))
      (node (ref "C135") (pin "1") (pinfunction "1_1") (pintype "passive"))
      (node (ref "C136") (pin "1") (pinfunction "1_1") (pintype "passive"))
      (node (ref "C137") (pin "1") (pinfunction "1_1") (pintype "passive"))
      (node (ref "C138") (pin "1") (pinfunction "1_1") (pintype "passive"))
      (node (ref "C139") (pin "1") (pinfunction "1_1") (pintype "passive"))
      (node (ref "R16") (pin "1") (pinfunction "1_1") (pintype "passive"))
      (node (ref "R17") (pin "1") (pinfunction "1_1") (pintype "passive"))
    )
    (net (code "124") (name "Net-(U8D-DDR1PLL_AVDD_0V9)") (class "Default")
      (node (ref "FB4") (pin "1") (pinfunction "1_1") (pintype "passive"))
      (node (ref "U8") (pin "H14") (pinfunction "DDR1PLL_AVDD_0V9_H14") (pintype "passive"))
    )
    (net (code "125") (name "Net-(U8D-DDR1_CLK_VDD)") (class "Default")
      (node (ref "FB5") (pin "1") (pinfunction "1_1") (pintype "passive"))
      (node (ref "U8") (pin "G12") (pinfunction "DDR1_CLK_VDD_G12") (pintype "passive"))
    )
    (net (code "126") (name "Net-(U8D-DDR1_PZQ)") (class "Default")
      (node (ref "R16") (pin "2") (pinfunction "2_2") (pintype "passive"))
      (node (ref "U8") (pin "G15") (pinfunction "DDR1_PZQ_G15") (pintype "passive"))
    )
    (net (code "127") (name "Net-(U8E-DDR0PLL_AVDD_0V9)") (class "Default")
      (node (ref "FB6") (pin "1") (pinfunction "1_1") (pintype "passive"))
      (node (ref "U8") (pin "R8") (pinfunction "DDR0PLL_AVDD_0V9_R8") (pintype "passive"))
    )
    (net (code "128") (name "Net-(U8E-DDR0_CLK_VDD)") (class "Default")
      (node (ref "FB7") (pin "1") (pinfunction "1_1") (pintype "passive"))
      (node (ref "U8") (pin "M7") (pinfunction "DDR0_CLK_VDD_M7") (pintype "passive"))
    )
    (net (code "129") (name "Net-(U8E-DDR0_PZQ)") (class "Default")
      (node (ref "R17") (pin "2") (pinfunction "2_2") (pintype "passive"))
      (node (ref "U8") (pin "R7") (pinfunction "DDR0_PZQ_R7") (pintype "passive"))
    )
    (net (code "130") (name "VCC_0V9") (class "Default")
      (node (ref "FB4") (pin "2") (pinfunction "2_2") (pintype "passive"))
      (node (ref "FB6") (pin "2") (pinfunction "2_2") (pintype "passive"))
    )
    (net (code "131") (name "VCC_DDR") (class "Default")
      (node (ref "C120") (pin "2") (pinfunction "2_2") (pintype "passive"))
      (node (ref "C121") (pin "2") (pinfunction "2_2") (pintype "passive"))
      (node (ref "C122") (pin "2") (pinfunction "2_2") (pintype "passive"))
      (node (ref "C123") (pin "2") (pinfunction "2_2") (pintype "passive"))
      (node (ref "C124") (pin "2") (pinfunction "2_2") (pintype "passive"))
      (node (ref "C125") (pin "2") (pinfunction "2_2") (pintype "passive"))
      (node (ref "C126") (pin "2") (pinfunction "2_2") (pintype "passive"))
      (node (ref "C127") (pin "2") (pinfunction "2_2") (pintype "passive"))
      (node (ref "C128") (pin "2") (pinfunction "2_2") (pintype "passive"))
      (node (ref "C129") (pin "2") (pinfunction "2_2") (pintype "passive"))
      (node (ref "C130") (pin "2") (pinfunction "2_2") (pintype "passive"))
      (node (ref "C131") (pin "2") (pinfunction "2_2") (pintype "passive"))
      (node (ref "C132") (pin "2") (pinfunction "2_2") (pintype "passive"))
      (node (ref "C133") (pin "2") (pinfunction "2_2") (pintype "passive"))
      (node (ref "C134") (pin "2") (pinfunction "2_2") (pintype "passive"))
      (node (ref "C135") (pin "2") (pinfunction "2_2") (pintype "passive"))
      (node (ref "C136") (pin "2") (pinfunction "2_2") (pintype "passive"))
      (node (ref "C137") (pin "2") (pinfunction "2_2") (pintype "passive"))
      (node (ref "C138") (pin "2") (pinfunction "2_2") (pintype "passive"))
      (node (ref "C139") (pin "2") (pinfunction "2_2") (pintype "passive"))
      (node (ref "FB5") (pin "2") (pinfunction "2_2") (pintype "passive"))
      (node (ref "FB7") (pin "2") (pinfunction "2_2") (pintype "passive"))
      (node (ref "U8") (pin "J11") (pinfunction "DDR1_VDD_1_J11") (pintype "passive"))
      (node (ref "U8") (pin "J12") (pinfunction "DDR1_VDD_2_J12") (pintype "passive"))
      (node (ref "U8") (pin "J13") (pinfunction "DDR1_VDD_3_J13") (pintype "passive"))
      (node (ref "U8") (pin "J14") (pinfunction "DDR1_VDD_4_J14") (pintype "passive"))
      (node (ref "U8") (pin "J15") (pinfunction "DDR1_VDD_5_J15") (pintype "passive"))
      (node (ref "U8") (pin "J16") (pinfunction "DDR1_VDD_6_J16") (pintype "passive"))
      (node (ref "U8") (pin "J17") (pinfunction "DDR1_VDD_7_J17") (pintype "passive"))
      (node (ref "U8") (pin "J18") (pinfunction "DDR1_VDD_8_J18") (pintype "passive"))
      (node (ref "U8") (pin "K11") (pinfunction "DDR1_VDD_9_K11") (pintype "passive"))
      (node (ref "U8") (pin "K13") (pinfunction "DDR1_VDD_10_K13") (pintype "passive"))
      (node (ref "U8") (pin "K15") (pinfunction "DDR1_VDD_11_K15") (pintype "passive"))
      (node (ref "U8") (pin "K17") (pinfunction "DDR1_VDD_12_K17") (pintype "passive"))
      (node (ref "U8") (pin "L10") (pinfunction "DDR0_VDD_2_L10") (pintype "passive"))
      (node (ref "U8") (pin "L9") (pinfunction "DDR0_VDD_1_L9") (pintype "passive"))
      (node (ref "U8") (pin "M9") (pinfunction "DDR0_VDD_3_M9") (pintype "passive"))
      (node (ref "U8") (pin "N10") (pinfunction "DDR0_VDD_5_N10") (pintype "passive"))
      (node (ref "U8") (pin "N9") (pinfunction "DDR0_VDD_4_N9") (pintype "passive"))
      (node (ref "U8") (pin "P9") (pinfunction "DDR0_VDD_6_P9") (pintype "passive"))
      (node (ref "U8") (pin "R10") (pinfunction "DDR0_VDD_8_R10") (pintype "passive"))
      (node (ref "U8") (pin "R9") (pinfunction "DDR0_VDD_7_R9") (pintype "passive"))
      (node (ref "U8") (pin "T9") (pinfunction "DDR0_VDD_9_T9") (pintype "passive"))
      (node (ref "U8") (pin "U10") (pinfunction "DDR0_VDD_11_U10") (pintype "passive"))
      (node (ref "U8") (pin "U9") (pinfunction "DDR0_VDD_10_U9") (pintype "passive"))
      (node (ref "U8") (pin "V9") (pinfunction "DDR0_VDD_12_V9") (pintype "passive"))
    )
    (net (code "132") (name "unconnected-(U8D-DDR1_A6-PadB7)") (class "Default")
      (node (ref "U8") (pin "B7") (pinfunction "DDR1_A6_B7") (pintype "passive+no_connect"))
    )
    (net (code "133") (name "unconnected-(U8D-DDR1_A7-PadA7)") (class "Default")
      (node (ref "U8") (pin "A7") (pinfunction "DDR1_A7_A7") (pintype "passive+no_connect"))
    )
    (net (code "134") (name "unconnected-(U8D-DDR1_A8-PadB6)") (class "Default")
      (node (ref "U8") (pin "B6") (pinfunction "DDR1_A8_B6") (pintype "passive+no_connect"))
    )
    (net (code "135") (name "unconnected-(U8D-DDR1_A9-PadA6)") (class "Default")
      (node (ref "U8") (pin "A6") (pinfunction "DDR1_A9_A6") (pintype "passive+no_connect"))
    )
    (net (code "136") (name "unconnected-(U8D-DDR1_A10-PadA4)") (class "Default")
      (node (ref "U8") (pin "A4") (pinfunction "DDR1_A10_A4") (pintype "passive+no_connect"))
    )
    (net (code "137") (name "unconnected-(U8D-DDR1_A11-PadC5)") (class "Default")
      (node (ref "U8") (pin "C5") (pinfunction "DDR1_A11_C5") (pintype "passive+no_connect"))
    )
    (net (code "138") (name "unconnected-(U8D-DDR1_A12-PadA3)") (class "Default")
      (node (ref "U8") (pin "A3") (pinfunction "DDR1_A12_A3") (pintype "passive+no_connect"))
    )
    (net (code "139") (name "unconnected-(U8D-DDR1_A13-PadB4)") (class "Default")
      (node (ref "U8") (pin "B4") (pinfunction "DDR1_A13_B4") (pintype "passive+no_connect"))
    )
    (net (code "140") (name "unconnected-(U8D-DDR1_A14-PadC4)") (class "Default")
      (node (ref "U8") (pin "C4") (pinfunction "DDR1_A14_C4") (pintype "passive+no_connect"))
    )
    (net (code "141") (name "unconnected-(U8D-DDR1_A15-PadG8)") (class "Default")
      (node (ref "U8") (pin "G8") (pinfunction "DDR1_A15_G8") (pintype "passive+no_connect"))
    )
    (net (code "142") (name "unconnected-(U8D-DDR1_ATB0-PadF17)") (class "Default")
      (node (ref "U8") (pin "F17") (pinfunction "DDR1_ATB0_F17") (pintype "passive+no_connect"))
    )
    (net (code "143") (name "unconnected-(U8D-DDR1_ATB1-PadG17)") (class "Default")
      (node (ref "U8") (pin "G17") (pinfunction "DDR1_ATB1_G17") (pintype "passive+no_connect"))
    )
    (net (code "144") (name "unconnected-(U8D-DDR1_BA0-PadB2)") (class "Default")
      (node (ref "U8") (pin "B2") (pinfunction "DDR1_BA0_B2") (pintype "passive+no_connect"))
    )
    (net (code "145") (name "unconnected-(U8D-DDR1_BA1-PadD6)") (class "Default")
      (node (ref "U8") (pin "D6") (pinfunction "DDR1_BA1_D6") (pintype "passive+no_connect"))
    )
    (net (code "146") (name "unconnected-(U8D-DDR1_BA2-PadD12)") (class "Default")
      (node (ref "U8") (pin "D12") (pinfunction "DDR1_BA2_D12") (pintype "passive+no_connect"))
    )
    (net (code "147") (name "unconnected-(U8D-DDR1_CASn-PadF9)") (class "Default")
      (node (ref "U8") (pin "F9") (pinfunction "DDR1_CASn_F9") (pintype "passive+no_connect"))
    )
    (net (code "148") (name "unconnected-(U8D-DDR1_ODT0-PadD11)") (class "Default")
      (node (ref "U8") (pin "D11") (pinfunction "DDR1_ODT0_D11") (pintype "passive+no_connect"))
    )
    (net (code "149") (name "unconnected-(U8D-DDR1_ODT1-PadE11)") (class "Default")
      (node (ref "U8") (pin "E11") (pinfunction "DDR1_ODT1_E11") (pintype "passive+no_connect"))
    )
    (net (code "150") (name "unconnected-(U8D-DDR1_PLL_TESTOUT_N-PadG14)") (class "Default")
      (node (ref "U8") (pin "G14") (pinfunction "DDR1_PLL_TESTOUT_N_G14") (pintype "passive+no_connect"))
    )
    (net (code "151") (name "unconnected-(U8D-DDR1_PLL_TESTOUT_P-PadF14)") (class "Default")
      (node (ref "U8") (pin "F14") (pinfunction "DDR1_PLL_TESTOUT_P_F14") (pintype "passive+no_connect"))
    )
    (net (code "152") (name "unconnected-(U8D-DDR1_RASn-PadC6)") (class "Default")
      (node (ref "U8") (pin "C6") (pinfunction "DDR1_RASn_C6") (pintype "passive+no_connect"))
    )
    (net (code "153") (name "unconnected-(U8D-DDR1_WEn-PadF7)") (class "Default")
      (node (ref "U8") (pin "F7") (pinfunction "DDR1_WEn_F7") (pintype "passive+no_connect"))
    )
    (net (code "154") (name "unconnected-(U8E-DDR0_A6-PadJ1)") (class "Default")
      (node (ref "U8") (pin "J1") (pinfunction "DDR0_A6_J1") (pintype "passive+no_connect"))
    )
    (net (code "155") (name "unconnected-(U8E-DDR0_A7-PadJ2)") (class "Default")
      (node (ref "U8") (pin "J2") (pinfunction "DDR0_A7_J2") (pintype "passive+no_connect"))
    )
    (net (code "156") (name "unconnected-(U8E-DDR0_A8-PadK2)") (class "Default")
      (node (ref "U8") (pin "K2") (pinfunction "DDR0_A8_K2") (pintype "passive+no_connect"))
    )
    (net (code "157") (name "unconnected-(U8E-DDR0_A9-PadK1)") (class "Default")
      (node (ref "U8") (pin "K1") (pinfunction "DDR0_A9_K1") (pintype "passive+no_connect"))
    )
    (net (code "158") (name "unconnected-(U8E-DDR0_A10-PadD1)") (class "Default")
      (node (ref "U8") (pin "D1") (pinfunction "DDR0_A10_D1") (pintype "passive+no_connect"))
    )
    (net (code "159") (name "unconnected-(U8E-DDR0_A11-PadE3)") (class "Default")
      (node (ref "U8") (pin "E3") (pinfunction "DDR0_A11_E3") (pintype "passive+no_connect"))
    )
    (net (code "160") (name "unconnected-(U8E-DDR0_A12-PadC1)") (class "Default")
      (node (ref "U8") (pin "C1") (pinfunction "DDR0_A12_C1") (pintype "passive+no_connect"))
    )
    (net (code "161") (name "unconnected-(U8E-DDR0_A13-PadD2)") (class "Default")
      (node (ref "U8") (pin "D2") (pinfunction "DDR0_A13_D2") (pintype "passive+no_connect"))
    )
    (net (code "162") (name "unconnected-(U8E-DDR0_A14-PadD3)") (class "Default")
      (node (ref "U8") (pin "D3") (pinfunction "DDR0_A14_D3") (pintype "passive+no_connect"))
    )
    (net (code "163") (name "unconnected-(U8E-DDR0_A15-PadH7)") (class "Default")
      (node (ref "U8") (pin "H7") (pinfunction "DDR0_A15_H7") (pintype "passive+no_connect"))
    )
    (net (code "164") (name "unconnected-(U8E-DDR0_ATB0-PadU6)") (class "Default")
      (node (ref "U8") (pin "U6") (pinfunction "DDR0_ATB0_U6") (pintype "passive+no_connect"))
    )
    (net (code "165") (name "unconnected-(U8E-DDR0_ATB1-PadU7)") (class "Default")
      (node (ref "U8") (pin "U7") (pinfunction "DDR0_ATB1_U7") (pintype "passive+no_connect"))
    )
    (net (code "166") (name "unconnected-(U8E-DDR0_BA0-PadC3)") (class "Default")
      (node (ref "U8") (pin "C3") (pinfunction "DDR0_BA0_C3") (pintype "passive+no_connect"))
    )
    (net (code "167") (name "unconnected-(U8E-DDR0_BA1-PadF4)") (class "Default")
      (node (ref "U8") (pin "F4") (pinfunction "DDR0_BA1_F4") (pintype "passive+no_connect"))
    )
    (net (code "168") (name "unconnected-(U8E-DDR0_BA2-PadM4)") (class "Default")
      (node (ref "U8") (pin "M4") (pinfunction "DDR0_BA2_M4") (pintype "passive+no_connect"))
    )
    (net (code "169") (name "unconnected-(U8E-DDR0_CASn-PadH6)") (class "Default")
      (node (ref "U8") (pin "H6") (pinfunction "DDR0_CASn_H6") (pintype "passive+no_connect"))
    )
    (net (code "170") (name "unconnected-(U8E-DDR0_ODT0-PadL4)") (class "Default")
      (node (ref "U8") (pin "L4") (pinfunction "DDR0_ODT0_L4") (pintype "passive+no_connect"))
    )
    (net (code "171") (name "unconnected-(U8E-DDR0_ODT1-PadL5)") (class "Default")
      (node (ref "U8") (pin "L5") (pinfunction "DDR0_ODT1_L5") (pintype "passive+no_connect"))
    )
    (net (code "172") (name "unconnected-(U8E-DDR0_PLL_TESTOUT_N-PadV7)") (class "Default")
      (node (ref "U8") (pin "V7") (pinfunction "DDR0_PLL_TESTOUT_N_V7") (pintype "passive+no_connect"))
    )
    (net (code "173") (name "unconnected-(U8E-DDR0_PLL_TESTOUT_P-PadV6)") (class "Default")
      (node (ref "U8") (pin "V6") (pinfunction "DDR0_PLL_TESTOUT_P_V6") (pintype "passive+no_connect"))
    )
    (net (code "174") (name "unconnected-(U8E-DDR0_RASn-PadF3)") (class "Default")
      (node (ref "U8") (pin "F3") (pinfunction "DDR0_RASn_F3") (pintype "passive+no_connect"))
    )
    (net (code "175") (name "unconnected-(U8E-DDR0_WEn-PadG6)") (class "Default")
      (node (ref "U8") (pin "G6") (pinfunction "DDR0_WEn_G6") (pintype "passive+no_connect"))
    )
  )
)
